# SCH_Card_2024-04-08.net
KiCad netlist of a schematic drawn in EasyEDA
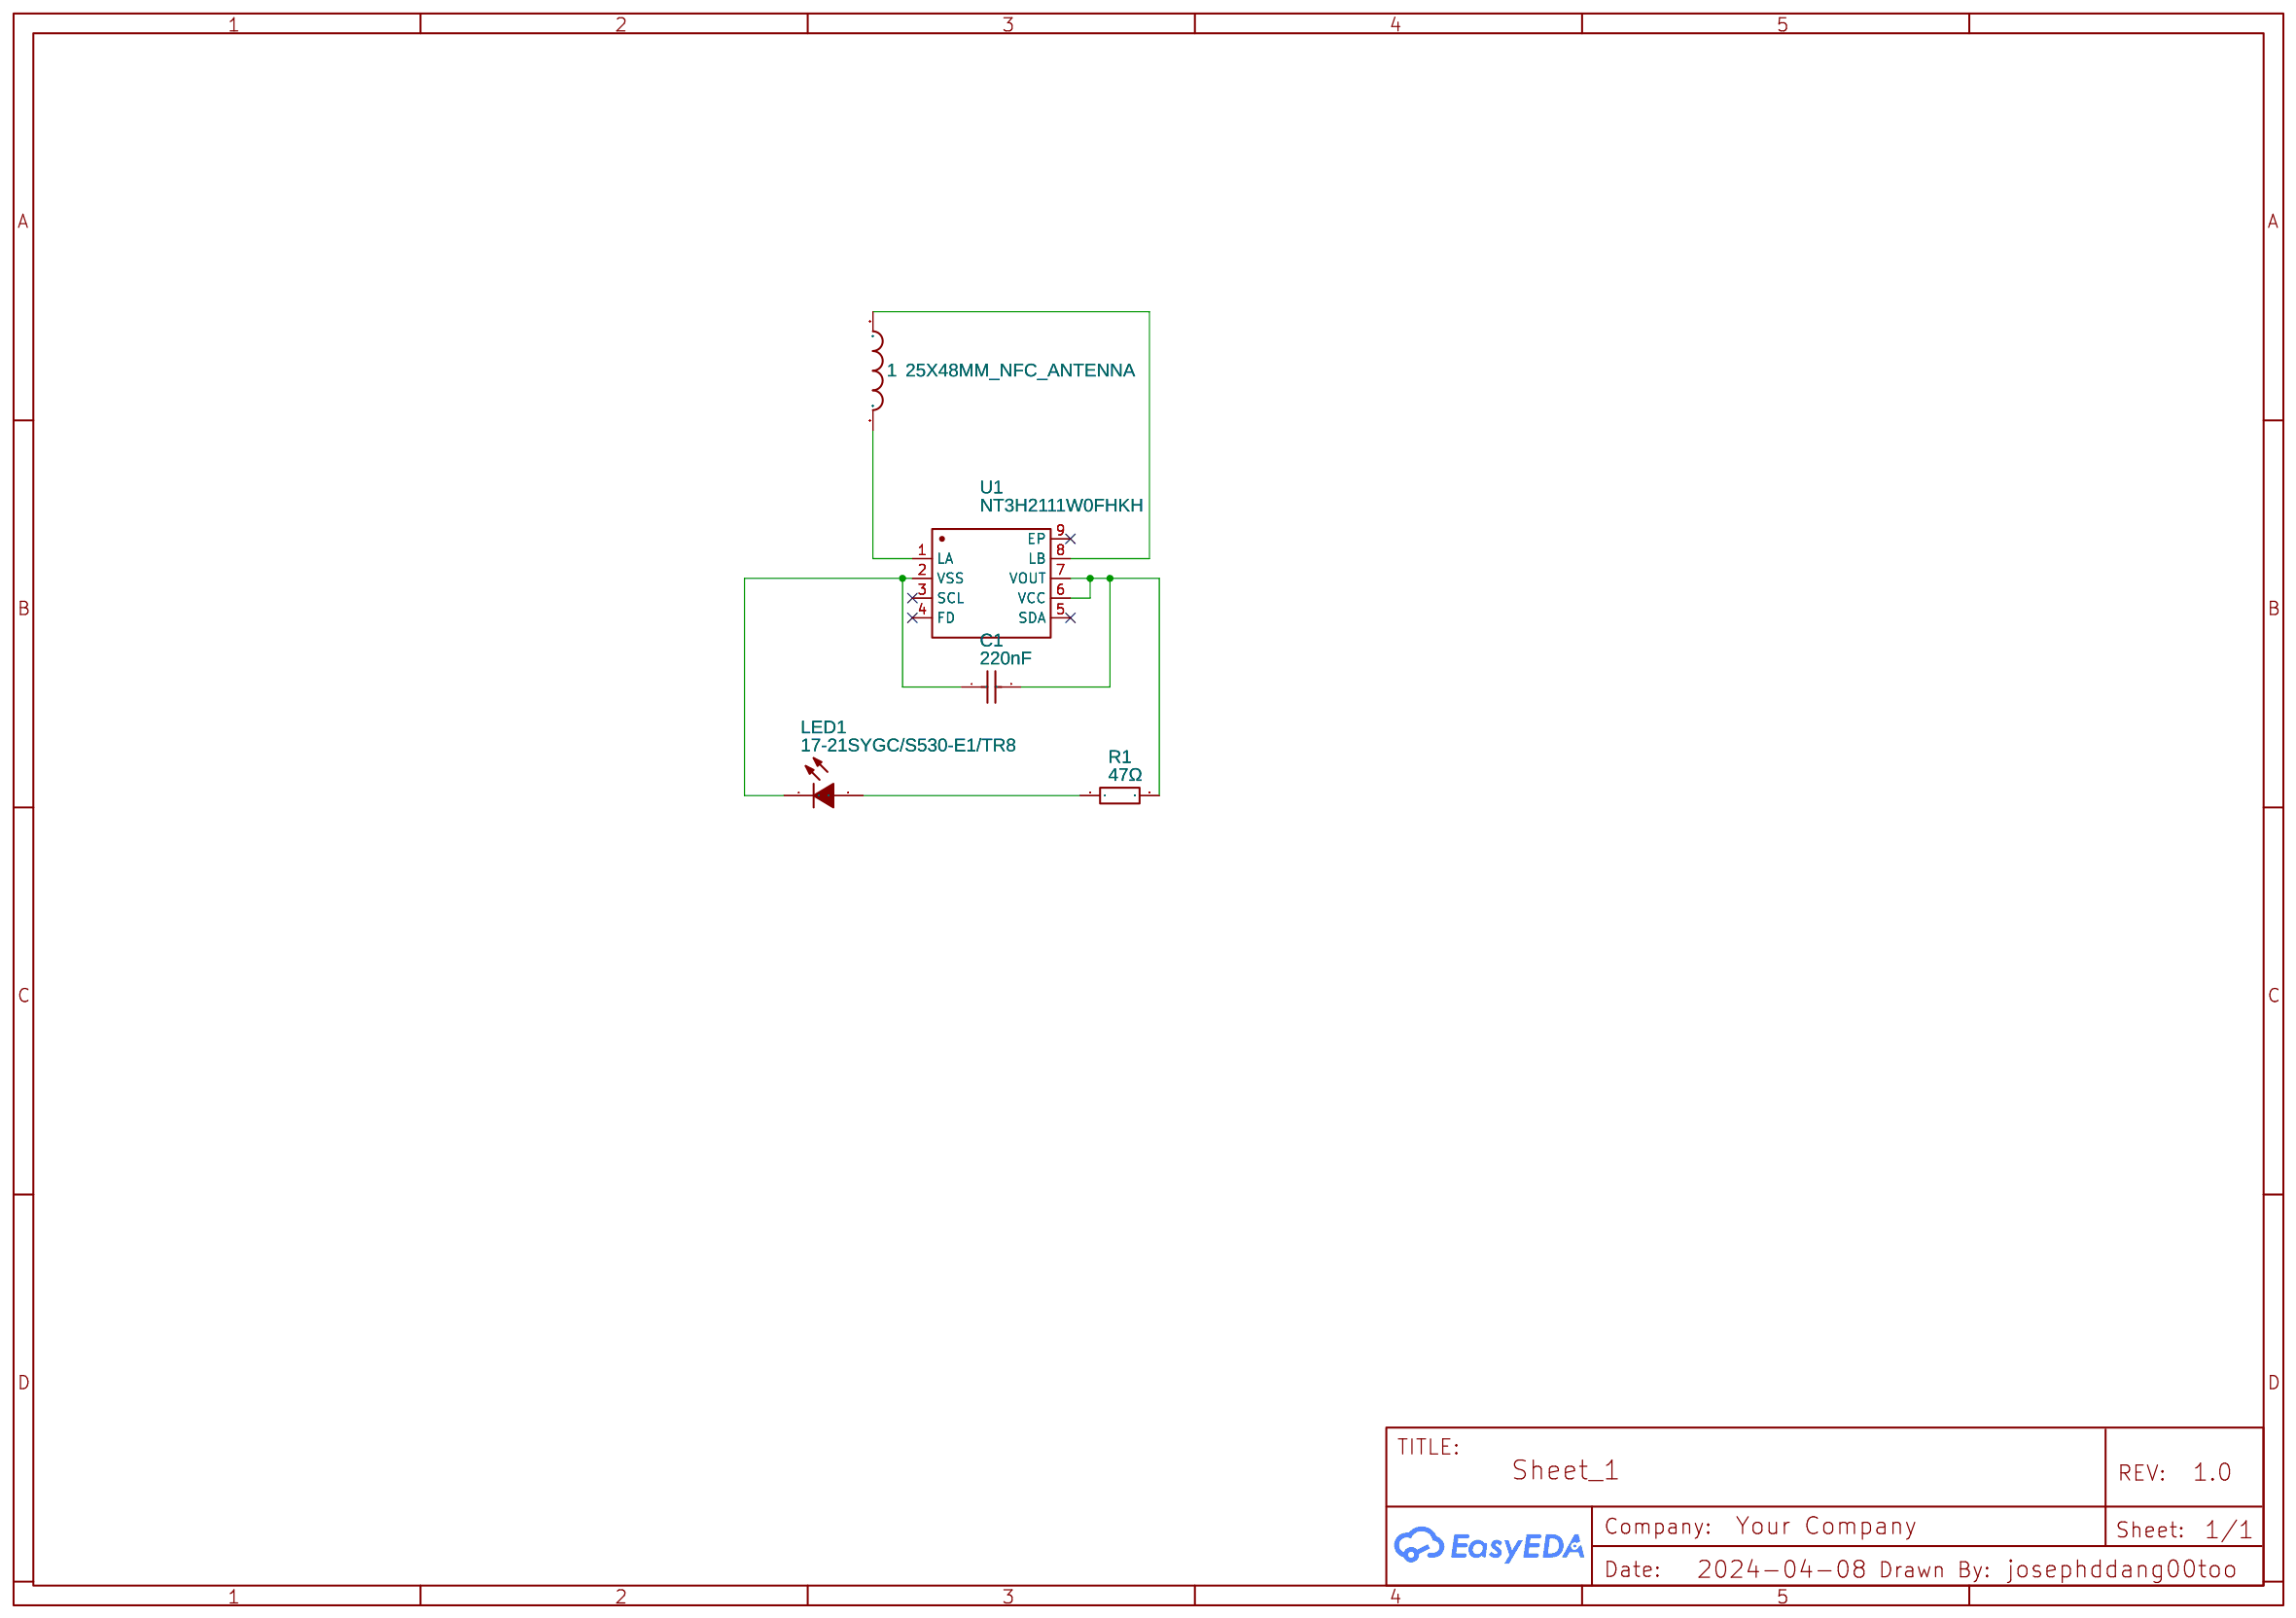
[diagram p0: schematic sheet]

(export (version "E")
  (design (tool "Eeschema 10.0.6"))
  (components
    (comp (ref "1") (value "25X48MM_NFC_ANTENNA") (libsource (lib "") (part "25X48MM_NFC_ANTENNA")))
    (comp (ref "C1")
      (value "220nF")
      (fields
        (field (name "Manufacturer Part") "CL10B224KA8NNNC")
        (field (name "Manufacturer") "SAMSUNG(三星)")
      )
      (libsource (lib "") (part "CL10B224KA8NNNC"))
    )
    (comp (ref "LED1")
      (value "17-21SYGC/S530-E1/TR8")
      (fields (field (name "Manufacturer") "EVERLIGHT(亿光)"))
      (libsource (lib "") (part "17-21SYGC/S530-E1/TR8"))
    )
    (comp (ref "R1")
      (value "47Ω")
      (fields
        (field (name "Manufacturer Part") "0603WAF470JT5E")
        (field (name "Manufacturer") "UNI-ROYAL(厚声)")
      )
      (libsource (lib "") (part "0603WAF470JT5E"))
    )
    (comp (ref "U1")
      (value "NT3H2111W0FHKH")
      (fields (field (name "Manufacturer") "NXP(恩智浦)"))
      (libsource (lib "") (part "NT3H2111W0FHKH"))
    )
  )
  (nets
    (net (code "1") (name "Net-(LED1-A)") (class "Default")
      (node (ref "LED1") (pin "1") (pinfunction "A_1") (pintype "input"))
      (node (ref "R1") (pin "1") (pinfunction "1_1") (pintype "input"))
    )
    (net (code "2") (name "Net-(LED1-C)") (class "Default")
      (node (ref "C1") (pin "1") (pinfunction "1_1") (pintype "input"))
      (node (ref "LED1") (pin "2") (pinfunction "C_2") (pintype "input"))
      (node (ref "U1") (pin "2") (pinfunction "VSS_2") (pintype "unspecified"))
    )
    (net (code "3") (name "Net-(U1-LA)") (class "Default")
      (node (ref "1") (pin "P$2") (pinfunction "P$2_P$2") (pintype "bidirectional"))
      (node (ref "U1") (pin "1") (pinfunction "LA_1") (pintype "unspecified"))
    )
    (net (code "4") (name "Net-(U1-LB)") (class "Default")
      (node (ref "1") (pin "P$1") (pinfunction "P$1_P$1") (pintype "bidirectional"))
      (node (ref "U1") (pin "8") (pinfunction "LB_8") (pintype "unspecified"))
    )
    (net (code "5") (name "Net-(U1-VCC)") (class "Default")
      (node (ref "C1") (pin "2") (pinfunction "2_2") (pintype "input"))
      (node (ref "R1") (pin "2") (pinfunction "2_2") (pintype "input"))
      (node (ref "U1") (pin "6") (pinfunction "VCC_6") (pintype "unspecified"))
      (node (ref "U1") (pin "7") (pinfunction "VOUT_7") (pintype "unspecified"))
    )
    (net (code "6") (name "unconnected-(U1-EP-Pad9)") (class "Default")
      (node (ref "U1") (pin "9") (pinfunction "EP_9") (pintype "unspecified+no_connect"))
    )
    (net (code "7") (name "unconnected-(U1-FD-Pad4)") (class "Default")
      (node (ref "U1") (pin "4") (pinfunction "FD_4") (pintype "unspecified+no_connect"))
    )
    (net (code "8") (name "unconnected-(U1-SCL-Pad3)") (class "Default")
      (node (ref "U1") (pin "3") (pinfunction "SCL_3") (pintype "unspecified+no_connect"))
    )
    (net (code "9") (name "unconnected-(U1-SDA-Pad5)") (class "Default")
      (node (ref "U1") (pin "5") (pinfunction "SDA_5") (pintype "unspecified+no_connect"))
    )
  )
)
